# ATRACK_WIFI_V1.net
KiCad netlist of a schematic drawn in Altium Designer
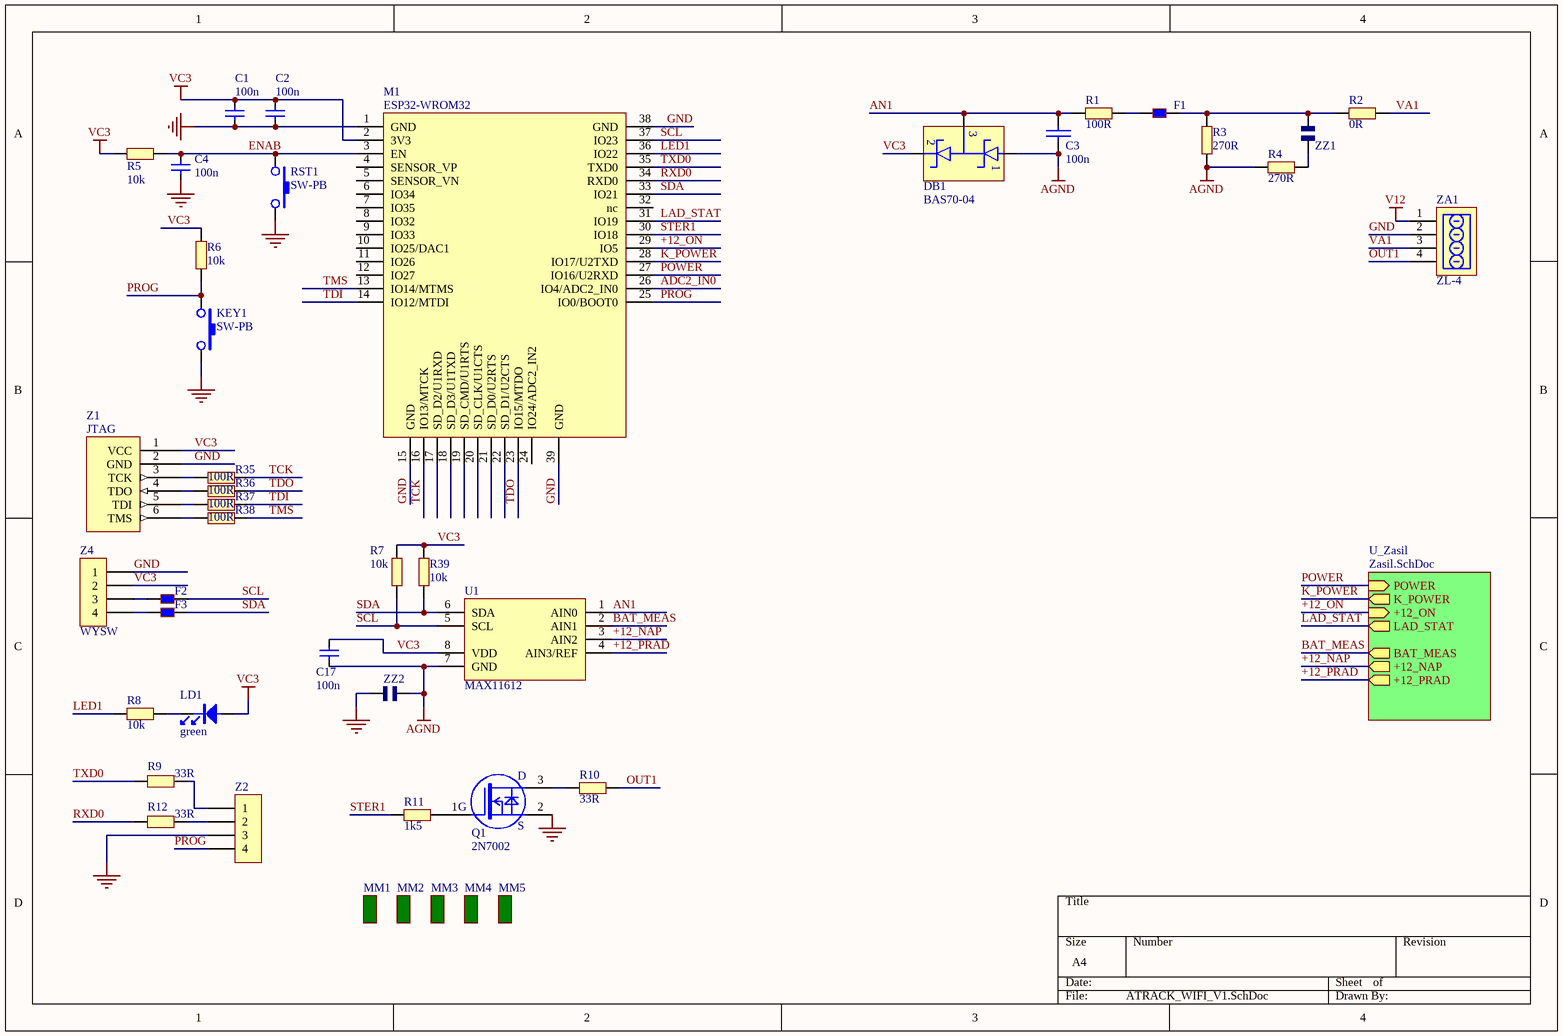
[diagram p0: ATRACK_WIFI_V1.SchDoc]

(export (version "E")
  (design (tool "Eeschema 10.0.6"))
  (components
    (comp (ref "C1") (value "100n") (footprint "0603C") (libsource (lib "*") (part "CAP")))
    (comp (ref "C2") (value "100n") (footprint "0603C") (libsource (lib "*") (part "CAP")))
    (comp (ref "C3")
      (value "100n")
      (footprint "0603C")
      (description "Capacitor")
      (libsource (lib "") (part "CAP_1"))
    )
    (comp (ref "C4") (value "100n") (footprint "0603C") (libsource (lib "*") (part "CAP")))
    (comp (ref "C17") (value "100n") (footprint "0603C") (libsource (lib "*") (part "CAP")))
    (comp (ref "DB1") (value "BAS70-04") (footprint "SOT-23") (libsource (lib "*") (part "BAS70-04")))
    (comp (ref "F1")
      (value "~")
      (footprint "0603L")
      (description "Koralik ferrytowy")
      (libsource (lib "*") (part "KORALIK"))
    )
    (comp (ref "F2")
      (value "BLM18BB141SN1D")
      (footprint "0603R")
      (description "Koralik ferrytowy")
      (libsource (lib "*") (part "1812"))
    )
    (comp (ref "F3")
      (value "BLM18BB141SN1D")
      (footprint "0603R")
      (description "Koralik ferrytowy")
      (libsource (lib "*") (part "1812"))
    )
    (comp (ref "KEY1") (value "SW-PB") (footprint "DTSM31N_2") (libsource (lib "*") (part "SW-PB")))
    (comp (ref "LD1")
      (value "green")
      (footprint "0603D")
      (description "LED,red,0603,19-213-R6C-AP1Q2B/3T,everlight")
      (libsource (lib "GkSchlib") (part "LED"))
    )
    (comp (ref "M1")
      (value "ESP32-WROM32")
      (footprint "ESP32-WROM32")
      (libsource (lib "GkSchlib") (part "ESP32-WROM32"))
    )
    (comp (ref "MM1") (value "~") (footprint "REF_CIR") (libsource (lib "*") (part "MECH")))
    (comp (ref "MM2") (value "~") (footprint "REF_CIR") (libsource (lib "*") (part "MECH")))
    (comp (ref "MM3") (value "~") (footprint "REF_SQR") (libsource (lib "*") (part "MECH")))
    (comp (ref "MM4") (value "~") (footprint "REF_SQR") (libsource (lib "*") (part "MECH")))
    (comp (ref "MM5") (value "~") (footprint "PB_FREE_GRAF") (libsource (lib "*") (part "MECH")))
    (comp (ref "Q1") (value "2N7002") (footprint "SOT23") (libsource (lib "*") (part "MOSFET-P_1_1")))
    (comp (ref "R1") (value "100R") (footprint "0603R") (libsource (lib "*") (part "RES3")))
    (comp (ref "R2") (value "0R") (footprint "0603R") (libsource (lib "*") (part "RES3")))
    (comp (ref "R3") (value "270R") (footprint "0603R") (libsource (lib "") (part "RES3_1")))
    (comp (ref "R4") (value "270R") (footprint "0603R") (libsource (lib "*") (part "RES3")))
    (comp (ref "R5") (value "10k") (footprint "0603R") (libsource (lib "*") (part "RES3")))
    (comp (ref "R6") (value "10k") (footprint "0603R") (libsource (lib "") (part "RES3_1")))
    (comp (ref "R7") (value "10k") (footprint "0603R") (libsource (lib "") (part "RES3_1")))
    (comp (ref "R8") (value "10k") (footprint "0603R") (libsource (lib "") (part "RES3_2")))
    (comp (ref "R9") (value "33R") (footprint "0603R") (libsource (lib "*") (part "RES3")))
    (comp (ref "R10") (value "33R") (footprint "0603R") (libsource (lib "") (part "RES3_3")))
    (comp (ref "R11") (value "1k5") (footprint "0603R") (libsource (lib "") (part "RES3_3")))
    (comp (ref "R12") (value "33R") (footprint "0603R") (libsource (lib "*") (part "RES3")))
    (comp (ref "R35") (value "100R") (footprint "0603R") (libsource (lib "*") (part "RES3")))
    (comp (ref "R36") (value "100R") (footprint "0603R") (libsource (lib "*") (part "RES3")))
    (comp (ref "R37") (value "100R") (footprint "0603R") (libsource (lib "*") (part "RES3")))
    (comp (ref "R38") (value "100R") (footprint "0603R") (libsource (lib "*") (part "RES3")))
    (comp (ref "R39") (value "10k") (footprint "0603R") (libsource (lib "") (part "RES3_1")))
    (comp (ref "RST1") (value "SW-PB") (footprint "DTSM31N_2") (libsource (lib "*") (part "SW-PB")))
    (comp (ref "U1") (value "MAX11612") (footprint "uMAX8") (libsource (lib "GkSchlib") (part "MAX11612")))
    (comp (ref "Z1") (value "JTAG") (footprint "PIN6") (libsource (lib "*") (part "Pro1F9.tmp_JTAG_64")))
    (comp (ref "Z2")
      (value "~")
      (footprint "PIN4")
      (description "Connector")
      (libsource (lib "") (part "CON4_1"))
    )
    (comp (ref "Z4")
      (value "WYSW")
      (footprint "UMATCH-4")
      (description "Connector")
      (libsource (lib "*") (part "CON4"))
    )
    (comp (ref "ZA1") (value "ZL-4") (footprint "PIN4_2.5") (libsource (lib "*") (part "ZL-4")))
    (comp (ref "ZZ1") (value "~") (footprint "ZW1") (libsource (lib "") (part "ZWORA_1")))
    (comp (ref "ZZ2") (value "~") (footprint "ZW1") (libsource (lib "*") (part "ZWORA")))
  )
  (nets
    (net (code "1") (name "/+12_NAP") (class "Default")
      (node (ref "U1") (pin "3") (pinfunction "AIN2_3") (pintype "passive"))
    )
    (net (code "2") (name "/+12_ON") (class "Default")
      (node (ref "M1") (pin "29") (pinfunction "IO5_29") (pintype "passive"))
    )
    (net (code "3") (name "/+12_PRAD") (class "Default")
      (node (ref "U1") (pin "4") (pinfunction "AIN3/REF_4") (pintype "passive"))
    )
    (net (code "4") (name "/ADC2_IN0") (class "Default")
      (node (ref "M1") (pin "26") (pinfunction "IO4/ADC2_IN0_26") (pintype "passive"))
    )
    (net (code "5") (name "/AN1") (class "Default")
      (node (ref "C3") (pin "1") (pinfunction "1_1") (pintype "passive"))
      (node (ref "DB1") (pin "3") (pintype "passive"))
      (node (ref "R1") (pin "2") (pintype "passive"))
      (node (ref "U1") (pin "1") (pinfunction "AIN0_1") (pintype "passive"))
    )
    (net (code "6") (name "/BAT_MEAS") (class "Default")
      (node (ref "U1") (pin "2") (pinfunction "AIN1_2") (pintype "passive"))
    )
    (net (code "7") (name "/ENAB") (class "Default")
      (node (ref "C4") (pin "1") (pintype "passive"))
      (node (ref "M1") (pin "3") (pinfunction "EN_3") (pintype "passive"))
      (node (ref "R5") (pin "1") (pintype "passive"))
      (node (ref "RST1") (pin "1") (pinfunction "1_1") (pintype "passive"))
    )
    (net (code "8") (name "/K_POWER") (class "Default")
      (node (ref "M1") (pin "28") (pinfunction "IO17/U2TXD_28") (pintype "passive"))
    )
    (net (code "9") (name "/LAD_STAT") (class "Default")
      (node (ref "M1") (pin "31") (pinfunction "IO19_31") (pintype "passive"))
    )
    (net (code "10") (name "/LED1") (class "Default")
      (node (ref "M1") (pin "36") (pinfunction "IO22_36") (pintype "passive"))
      (node (ref "R8") (pin "1") (pintype "passive"))
    )
    (net (code "11") (name "/OUT1") (class "Default")
      (node (ref "R10") (pin "2") (pintype "passive"))
      (node (ref "ZA1") (pin "4") (pintype "passive"))
    )
    (net (code "12") (name "/POWER") (class "Default")
      (node (ref "M1") (pin "27") (pinfunction "IO16/U2RXD_27") (pintype "passive"))
    )
    (net (code "13") (name "/PROG") (class "Default")
      (node (ref "KEY1") (pin "1") (pinfunction "1_1") (pintype "passive"))
      (node (ref "M1") (pin "25") (pinfunction "IO0/BOOT0_25") (pintype "passive"))
      (node (ref "R6") (pin "1") (pintype "passive"))
      (node (ref "Z2") (pin "4") (pinfunction "4_4") (pintype "passive"))
    )
    (net (code "14") (name "/RXD0") (class "Default")
      (node (ref "M1") (pin "34") (pinfunction "RXD0_34") (pintype "passive"))
      (node (ref "R12") (pin "2") (pintype "passive"))
    )
    (net (code "15") (name "/SCL") (class "Default")
      (node (ref "F2") (pin "2") (pintype "passive"))
      (node (ref "M1") (pin "37") (pinfunction "IO23_37") (pintype "passive"))
      (node (ref "R7") (pin "1") (pintype "passive"))
      (node (ref "U1") (pin "5") (pinfunction "SCL_5") (pintype "passive"))
    )
    (net (code "16") (name "/SDA") (class "Default")
      (node (ref "F3") (pin "2") (pintype "passive"))
      (node (ref "M1") (pin "33") (pinfunction "IO21_33") (pintype "passive"))
      (node (ref "R39") (pin "1") (pintype "passive"))
      (node (ref "U1") (pin "6") (pinfunction "SDA_6") (pintype "passive"))
    )
    (net (code "17") (name "/STER1") (class "Default")
      (node (ref "M1") (pin "30") (pinfunction "IO18_30") (pintype "passive"))
      (node (ref "R11") (pin "1") (pintype "passive"))
    )
    (net (code "18") (name "/TCK") (class "Default")
      (node (ref "M1") (pin "16") (pinfunction "IO13/MTCK_16") (pintype "passive"))
      (node (ref "R35") (pin "1") (pintype "passive"))
    )
    (net (code "19") (name "/TDI") (class "Default")
      (node (ref "M1") (pin "14") (pinfunction "IO12/MTDI_14") (pintype "passive"))
      (node (ref "R37") (pin "1") (pintype "passive"))
    )
    (net (code "20") (name "/TDO") (class "Default")
      (node (ref "M1") (pin "23") (pinfunction "IO15/MTDO_23") (pintype "passive"))
      (node (ref "R36") (pin "1") (pintype "passive"))
    )
    (net (code "21") (name "/TMS") (class "Default")
      (node (ref "M1") (pin "13") (pinfunction "IO14/MTMS_13") (pintype "passive"))
      (node (ref "R38") (pin "1") (pintype "passive"))
    )
    (net (code "22") (name "/TXD0") (class "Default")
      (node (ref "M1") (pin "35") (pinfunction "TXD0_35") (pintype "passive"))
      (node (ref "R9") (pin "2") (pintype "passive"))
    )
    (net (code "23") (name "/VA1") (class "Default")
      (node (ref "R2") (pin "1") (pintype "passive"))
      (node (ref "ZA1") (pin "3") (pintype "passive"))
    )
    (net (code "24") (name "AGND") (class "Default")
      (node (ref "C17") (pin "2") (pintype "passive"))
      (node (ref "C3") (pin "2") (pinfunction "2_2") (pintype "passive"))
      (node (ref "DB1") (pin "1") (pintype "passive"))
      (node (ref "R3") (pin "1") (pintype "passive"))
      (node (ref "R4") (pin "2") (pintype "passive"))
      (node (ref "U1") (pin "7") (pinfunction "GND_7") (pintype "passive"))
      (node (ref "ZZ2") (pin "1") (pintype "passive"))
    )
    (net (code "25") (name "GND") (class "Default")
      (node (ref "C1") (pin "1") (pintype "passive"))
      (node (ref "C2") (pin "1") (pintype "passive"))
      (node (ref "C4") (pin "2") (pintype "passive"))
      (node (ref "KEY1") (pin "2") (pinfunction "2_2") (pintype "passive"))
      (node (ref "M1") (pin "1") (pinfunction "GND_1") (pintype "passive"))
      (node (ref "M1") (pin "15") (pinfunction "GND_15") (pintype "passive"))
      (node (ref "M1") (pin "38") (pinfunction "GND_38") (pintype "passive"))
      (node (ref "M1") (pin "39") (pinfunction "GND_39") (pintype "passive"))
      (node (ref "Q1") (pin "2") (pinfunction "S_2") (pintype "passive"))
      (node (ref "RST1") (pin "2") (pinfunction "2_2") (pintype "passive"))
      (node (ref "Z1") (pin "2") (pinfunction "GND_2") (pintype "power_in"))
      (node (ref "Z2") (pin "3") (pinfunction "3_3") (pintype "passive"))
      (node (ref "Z4") (pin "1") (pinfunction "1_1") (pintype "passive"))
      (node (ref "ZA1") (pin "2") (pintype "passive"))
      (node (ref "ZZ2") (pin "2") (pintype "passive"))
    )
    (net (code "26") (name "Net-(F1-Pad1)") (class "Default")
      (node (ref "F1") (pin "1") (pintype "passive"))
      (node (ref "R1") (pin "1") (pintype "passive"))
    )
    (net (code "27") (name "Net-(F1-Pad2)") (class "Default")
      (node (ref "F1") (pin "2") (pintype "passive"))
      (node (ref "R2") (pin "2") (pintype "passive"))
      (node (ref "R3") (pin "2") (pintype "passive"))
      (node (ref "ZZ1") (pin "2") (pintype "passive"))
    )
    (net (code "28") (name "Net-(F2-Pad1)") (class "Default")
      (node (ref "F2") (pin "1") (pintype "passive"))
      (node (ref "Z4") (pin "3") (pinfunction "3_3") (pintype "passive"))
    )
    (net (code "29") (name "Net-(F3-Pad1)") (class "Default")
      (node (ref "F3") (pin "1") (pintype "passive"))
      (node (ref "Z4") (pin "4") (pinfunction "4_4") (pintype "passive"))
    )
    (net (code "30") (name "Net-(LD1-PadK)") (class "Default")
      (node (ref "LD1") (pin "K") (pintype "passive"))
      (node (ref "R8") (pin "2") (pintype "passive"))
    )
    (net (code "31") (name "Net-(Q1-D)") (class "Default")
      (node (ref "Q1") (pin "3") (pinfunction "D_3") (pintype "passive"))
      (node (ref "R10") (pin "1") (pintype "passive"))
    )
    (net (code "32") (name "Net-(Q1-Pad1)") (class "Default")
      (node (ref "Q1") (pin "1") (pinfunction "1_1") (pintype "passive"))
      (node (ref "R11") (pin "2") (pintype "passive"))
    )
    (net (code "33") (name "Net-(R4-Pad1)") (class "Default")
      (node (ref "R4") (pin "1") (pintype "passive"))
      (node (ref "ZZ1") (pin "1") (pintype "passive"))
    )
    (net (code "34") (name "Net-(R9-Pad1)") (class "Default")
      (node (ref "R9") (pin "1") (pintype "passive"))
      (node (ref "Z2") (pin "1") (pinfunction "1_1") (pintype "passive"))
    )
    (net (code "35") (name "Net-(R12-Pad1)") (class "Default")
      (node (ref "R12") (pin "1") (pintype "passive"))
      (node (ref "Z2") (pin "2") (pinfunction "2_2") (pintype "passive"))
    )
    (net (code "36") (name "Net-(Z1-TCK)") (class "Default")
      (node (ref "R35") (pin "2") (pintype "passive"))
      (node (ref "Z1") (pin "3") (pinfunction "TCK_3") (pintype "output"))
    )
    (net (code "37") (name "Net-(Z1-TDI)") (class "Default")
      (node (ref "R37") (pin "2") (pintype "passive"))
      (node (ref "Z1") (pin "5") (pinfunction "TDI_5") (pintype "output"))
    )
    (net (code "38") (name "Net-(Z1-TDO)") (class "Default")
      (node (ref "R36") (pin "2") (pintype "passive"))
      (node (ref "Z1") (pin "4") (pinfunction "TDO_4") (pintype "input"))
    )
    (net (code "39") (name "Net-(Z1-TMS)") (class "Default")
      (node (ref "R38") (pin "2") (pintype "passive"))
      (node (ref "Z1") (pin "6") (pinfunction "TMS_6") (pintype "output"))
    )
    (net (code "40") (name "V12") (class "Default") (node (ref "ZA1") (pin "1") (pintype "passive")))
    (net (code "41") (name "VC3") (class "Default")
      (node (ref "C1") (pin "2") (pintype "passive"))
      (node (ref "C17") (pin "1") (pintype "passive"))
      (node (ref "C2") (pin "2") (pintype "passive"))
      (node (ref "DB1") (pin "2") (pintype "passive"))
      (node (ref "LD1") (pin "A") (pintype "passive"))
      (node (ref "M1") (pin "2") (pinfunction "3V3_2") (pintype "passive"))
      (node (ref "R39") (pin "2") (pintype "passive"))
      (node (ref "R5") (pin "2") (pintype "passive"))
      (node (ref "R6") (pin "2") (pintype "passive"))
      (node (ref "R7") (pin "2") (pintype "passive"))
      (node (ref "U1") (pin "8") (pinfunction "VDD_8") (pintype "passive"))
      (node (ref "Z1") (pin "1") (pinfunction "VCC_1") (pintype "power_in"))
      (node (ref "Z4") (pin "2") (pinfunction "2_2") (pintype "passive"))
    )
    (net (code "42") (name "unconnected-(M1-IO24{slash}ADC2_IN2-Pad24)") (class "Default")
      (node (ref "M1") (pin "24") (pinfunction "IO24/ADC2_IN2_24") (pintype "passive"))
    )
    (net (code "43") (name "unconnected-(M1-IO25{slash}DAC1-Pad10)") (class "Default")
      (node (ref "M1") (pin "10") (pinfunction "IO25/DAC1_10") (pintype "passive"))
    )
    (net (code "44") (name "unconnected-(M1-IO26-Pad11)") (class "Default")
      (node (ref "M1") (pin "11") (pinfunction "IO26_11") (pintype "passive"))
    )
    (net (code "45") (name "unconnected-(M1-IO27-Pad12)") (class "Default")
      (node (ref "M1") (pin "12") (pinfunction "IO27_12") (pintype "passive"))
    )
    (net (code "46") (name "unconnected-(M1-IO32-Pad8)") (class "Default")
      (node (ref "M1") (pin "8") (pinfunction "IO32_8") (pintype "passive"))
    )
    (net (code "47") (name "unconnected-(M1-IO33-Pad9)") (class "Default")
      (node (ref "M1") (pin "9") (pinfunction "IO33_9") (pintype "passive"))
    )
    (net (code "48") (name "unconnected-(M1-IO34-Pad6)") (class "Default")
      (node (ref "M1") (pin "6") (pinfunction "IO34_6") (pintype "passive"))
    )
    (net (code "49") (name "unconnected-(M1-IO35-Pad7)") (class "Default")
      (node (ref "M1") (pin "7") (pinfunction "IO35_7") (pintype "passive"))
    )
    (net (code "50") (name "unconnected-(M1-SD_CLK{slash}U1CTS-Pad20)") (class "Default")
      (node (ref "M1") (pin "20") (pinfunction "SD_CLK/U1CTS_20") (pintype "passive"))
    )
    (net (code "51") (name "unconnected-(M1-SD_CMD{slash}U1RTS-Pad19)") (class "Default")
      (node (ref "M1") (pin "19") (pinfunction "SD_CMD/U1RTS_19") (pintype "passive"))
    )
    (net (code "52") (name "unconnected-(M1-SD_D0{slash}U2RTS-Pad21)") (class "Default")
      (node (ref "M1") (pin "21") (pinfunction "SD_D0/U2RTS_21") (pintype "passive"))
    )
    (net (code "53") (name "unconnected-(M1-SD_D1{slash}U2CTS-Pad22)") (class "Default")
      (node (ref "M1") (pin "22") (pinfunction "SD_D1/U2CTS_22") (pintype "passive"))
    )
    (net (code "54") (name "unconnected-(M1-SD_D2{slash}U1RXD-Pad17)") (class "Default")
      (node (ref "M1") (pin "17") (pinfunction "SD_D2/U1RXD_17") (pintype "passive"))
    )
    (net (code "55") (name "unconnected-(M1-SD_D3{slash}U1TXD-Pad18)") (class "Default")
      (node (ref "M1") (pin "18") (pinfunction "SD_D3/U1TXD_18") (pintype "passive"))
    )
    (net (code "56") (name "unconnected-(M1-SENSOR_VN-Pad5)") (class "Default")
      (node (ref "M1") (pin "5") (pinfunction "SENSOR_VN_5") (pintype "passive"))
    )
    (net (code "57") (name "unconnected-(M1-SENSOR_VP-Pad4)") (class "Default")
      (node (ref "M1") (pin "4") (pinfunction "SENSOR_VP_4") (pintype "passive"))
    )
    (net (code "58") (name "unconnected-(M1-nc-Pad32)") (class "Default")
      (node (ref "M1") (pin "32") (pinfunction "nc_32") (pintype "passive"))
    )
  )
)
